# musesb.net
KiCad netlist of a schematic drawn in EAGLE
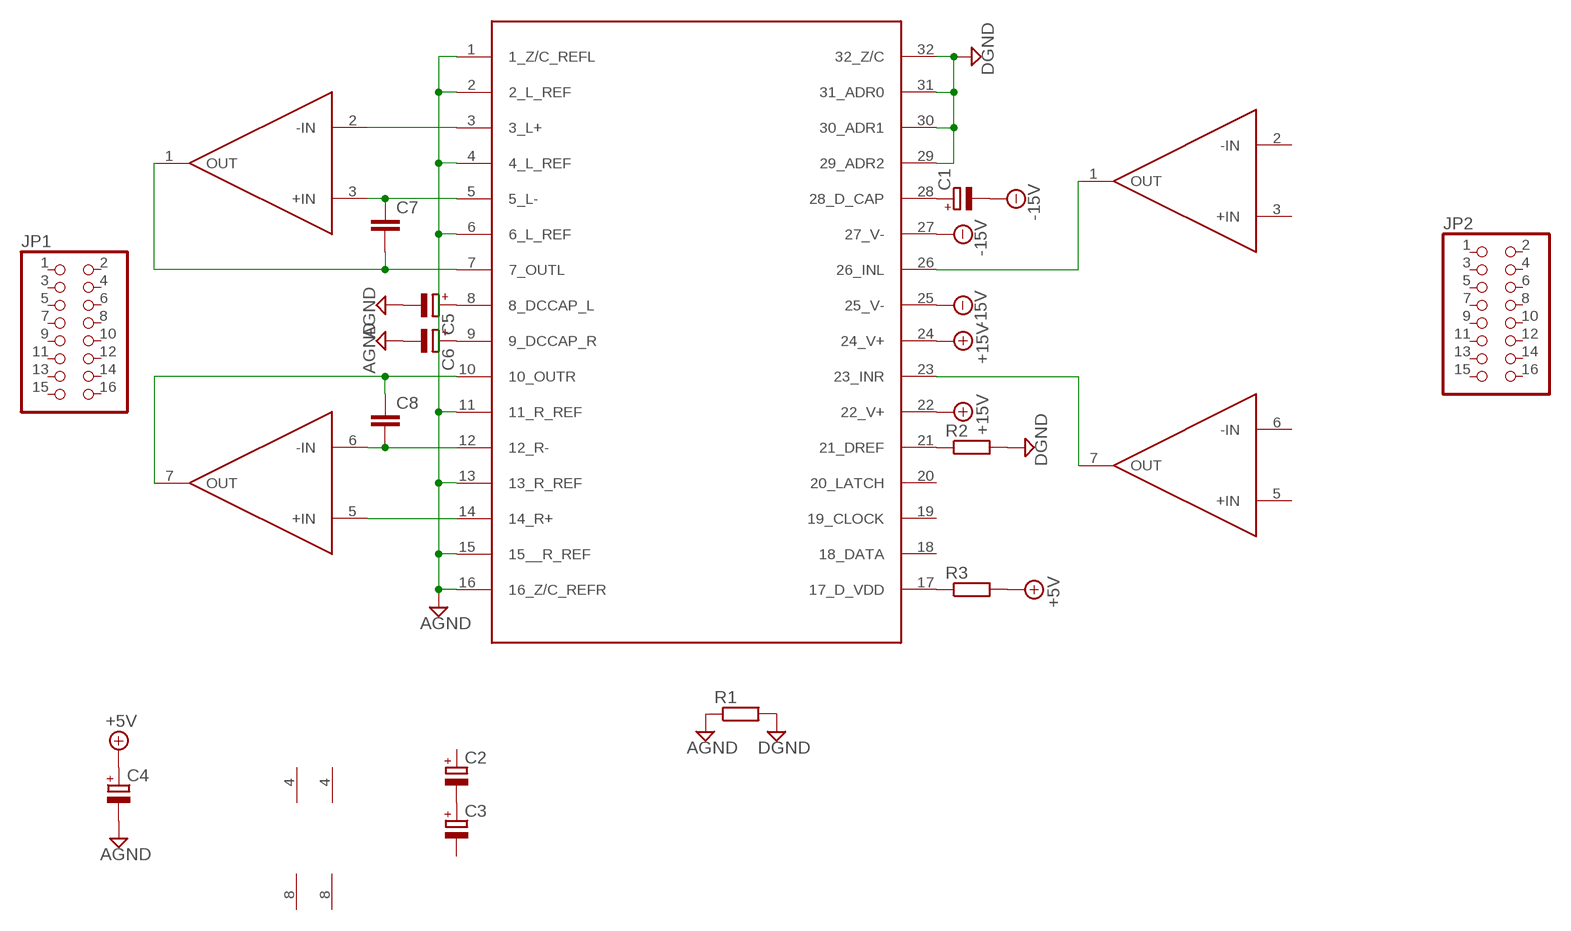
[diagram p0: schematic, sheet 1]

(export (version "E")
  (design (tool "Eeschema 10.0.6"))
  (components
    (comp (ref "C1")
      (value "CPOL-EUE2.5-6")
      (footprint "eagle-import:E2,5-6")
      (libsource (lib "eagle-import") (part "CPOL-EUE2.5-6"))
    )
    (comp (ref "C2")
      (value "CPOL-EUE3.5-8")
      (footprint "eagle-import:E3,5-8")
      (libsource (lib "eagle-import") (part "CPOL-EUE3.5-8"))
    )
    (comp (ref "C3")
      (value "CPOL-EUE3.5-8")
      (footprint "eagle-import:E3,5-8")
      (libsource (lib "eagle-import") (part "CPOL-EUE3.5-8"))
    )
    (comp (ref "C4")
      (value "CPOL-EUE3.5-8")
      (footprint "eagle-import:E3,5-8")
      (libsource (lib "eagle-import") (part "CPOL-EUE3.5-8"))
    )
    (comp (ref "C5")
      (value "CPOL-EUE3.5-8")
      (footprint "eagle-import:E3,5-8")
      (libsource (lib "eagle-import") (part "CPOL-EUE3.5-8"))
    )
    (comp (ref "C6")
      (value "CPOL-EUE3.5-8")
      (footprint "eagle-import:E3,5-8")
      (libsource (lib "eagle-import") (part "CPOL-EUE3.5-8"))
    )
    (comp (ref "C7")
      (value "C-EU025-025X050")
      (footprint "eagle-import:C025-025X050")
      (libsource (lib "eagle-import") (part "C-EU025-025X050"))
    )
    (comp (ref "C8")
      (value "C-EU025-025X050")
      (footprint "eagle-import:C025-025X050")
      (libsource (lib "eagle-import") (part "C-EU025-025X050"))
    )
    (comp (ref "JP1")
      (value "PINHD-2X8")
      (footprint "eagle-import:2X08")
      (libsource (lib "eagle-import") (part "PINHD-2X8"))
    )
    (comp (ref "JP2")
      (value "PINHD-2X8")
      (footprint "eagle-import:2X08")
      (libsource (lib "eagle-import") (part "PINHD-2X8"))
    )
    (comp (ref "R1")
      (value "R-EU_0207/7")
      (footprint "eagle-import:0207_7")
      (libsource (lib "eagle-import") (part "R-EU_0207/7"))
    )
    (comp (ref "R2")
      (value "R-EU_0207/7")
      (footprint "eagle-import:0207_7")
      (libsource (lib "eagle-import") (part "R-EU_0207/7"))
    )
    (comp (ref "R3")
      (value "R-EU_0207/7")
      (footprint "eagle-import:0207_7")
      (libsource (lib "eagle-import") (part "R-EU_0207/7"))
    )
    (comp (ref "U$1")
      (value "MUSES72320")
      (footprint "eagle-import:SSOP28DB")
      (libsource (lib "eagle-import") (part "MUSES72320"))
    )
    (comp (ref "U$2")
      (value "LME49720")
      (footprint "eagle-import:DIL08")
      (libsource (lib "eagle-import") (part "LME49720"))
    )
    (comp (ref "U$3")
      (value "LME49720")
      (footprint "eagle-import:DIL08")
      (libsource (lib "eagle-import") (part "LME49720"))
    )
  )
  (nets
    (net (code "1") (name "+5V") (class "Default")
      (node (ref "C4") (pin "+") (pinfunction "+_+") (pintype "passive"))
      (node (ref "R3") (pin "2") (pinfunction "2_2") (pintype "passive"))
    )
    (net (code "2") (name "+15V") (class "Default")
      (node (ref "U$1") (pin "22") (pinfunction "22_V+_22") (pintype "power_in"))
      (node (ref "U$1") (pin "24") (pinfunction "24_V+_24") (pintype "power_in"))
    )
    (net (code "3") (name "-15V") (class "Default")
      (node (ref "C1") (pin "-") (pinfunction "-_-") (pintype "passive"))
      (node (ref "U$1") (pin "25") (pinfunction "25_V-_25") (pintype "power_in"))
      (node (ref "U$1") (pin "27") (pinfunction "27_V-_27") (pintype "power_in"))
    )
    (net (code "4") (name "AGND") (class "Default")
      (node (ref "C4") (pin "-") (pinfunction "-_-") (pintype "passive"))
      (node (ref "C5") (pin "-") (pinfunction "-_-") (pintype "passive"))
      (node (ref "C6") (pin "-") (pinfunction "-_-") (pintype "passive"))
      (node (ref "R1") (pin "1") (pinfunction "1_1") (pintype "passive"))
      (node (ref "U$1") (pin "1") (pinfunction "1_Z/C_REFL_1") (pintype "power_in"))
      (node (ref "U$1") (pin "11") (pinfunction "11_R_REF_11") (pintype "power_in"))
      (node (ref "U$1") (pin "13") (pinfunction "13_R_REF_13") (pintype "power_in"))
      (node (ref "U$1") (pin "15") (pinfunction "15__R_REF_15") (pintype "power_in"))
      (node (ref "U$1") (pin "16") (pinfunction "16_Z/C_REFR_16") (pintype "power_in"))
      (node (ref "U$1") (pin "2") (pinfunction "2_L_REF_2") (pintype "power_in"))
      (node (ref "U$1") (pin "4") (pinfunction "4_L_REF_4") (pintype "power_in"))
      (node (ref "U$1") (pin "6") (pinfunction "6_L_REF_6") (pintype "power_in"))
    )
    (net (code "5") (name "DGND") (class "Default")
      (node (ref "R1") (pin "2") (pinfunction "2_2") (pintype "passive"))
      (node (ref "R2") (pin "2") (pinfunction "2_2") (pintype "passive"))
      (node (ref "U$1") (pin "29") (pinfunction "29_ADR2_29") (pintype "bidirectional"))
      (node (ref "U$1") (pin "30") (pinfunction "30_ADR1_30") (pintype "bidirectional"))
      (node (ref "U$1") (pin "31") (pinfunction "31_ADR0_31") (pintype "bidirectional"))
      (node (ref "U$1") (pin "32") (pinfunction "32_Z/C_32") (pintype "bidirectional"))
    )
    (net (code "6") (name "Net-(C2-Pad-)") (class "Default")
      (node (ref "C2") (pin "-") (pinfunction "-_-") (pintype "passive"))
      (node (ref "C3") (pin "+") (pinfunction "+_+") (pintype "passive"))
    )
    (net (code "7") (name "Net-(U$1-3_L+)") (class "Default")
      (node (ref "U$1") (pin "3") (pinfunction "3_L+_3") (pintype "bidirectional"))
      (node (ref "U$2") (pin "2") (pinfunction "-IN_2") (pintype "bidirectional"))
    )
    (net (code "8") (name "Net-(U$1-5_L-)") (class "Default")
      (node (ref "C7") (pin "1") (pinfunction "1_1") (pintype "passive"))
      (node (ref "U$1") (pin "5") (pinfunction "5_L-_5") (pintype "bidirectional"))
      (node (ref "U$2") (pin "3") (pinfunction "+IN_3") (pintype "bidirectional"))
    )
    (net (code "9") (name "Net-(U$1-7_OUTL)") (class "Default")
      (node (ref "C7") (pin "2") (pinfunction "2_2") (pintype "passive"))
      (node (ref "U$1") (pin "7") (pinfunction "7_OUTL_7") (pintype "bidirectional"))
      (node (ref "U$2") (pin "1") (pinfunction "OUT_1") (pintype "bidirectional"))
    )
    (net (code "10") (name "Net-(U$1-8_DCCAP_L)") (class "Default")
      (node (ref "C5") (pin "+") (pinfunction "+_+") (pintype "passive"))
      (node (ref "U$1") (pin "8") (pinfunction "8_DCCAP_L_8") (pintype "power_in"))
    )
    (net (code "11") (name "Net-(U$1-9_DCCAP_R)") (class "Default")
      (node (ref "C6") (pin "+") (pinfunction "+_+") (pintype "passive"))
      (node (ref "U$1") (pin "9") (pinfunction "9_DCCAP_R_9") (pintype "power_in"))
    )
    (net (code "12") (name "Net-(U$1-10_OUTR)") (class "Default")
      (node (ref "C8") (pin "1") (pinfunction "1_1") (pintype "passive"))
      (node (ref "U$1") (pin "10") (pinfunction "10_OUTR_10") (pintype "bidirectional"))
      (node (ref "U$2") (pin "7") (pinfunction "OUT_7") (pintype "bidirectional"))
    )
    (net (code "13") (name "Net-(U$1-12_R-)") (class "Default")
      (node (ref "C8") (pin "2") (pinfunction "2_2") (pintype "passive"))
      (node (ref "U$1") (pin "12") (pinfunction "12_R-_12") (pintype "bidirectional"))
      (node (ref "U$2") (pin "6") (pinfunction "-IN_6") (pintype "bidirectional"))
    )
    (net (code "14") (name "Net-(U$1-14_R+)") (class "Default")
      (node (ref "U$1") (pin "14") (pinfunction "14_R+_14") (pintype "bidirectional"))
      (node (ref "U$2") (pin "5") (pinfunction "+IN_5") (pintype "bidirectional"))
    )
    (net (code "15") (name "Net-(U$1-17_D_VDD)") (class "Default")
      (node (ref "R3") (pin "1") (pinfunction "1_1") (pintype "passive"))
      (node (ref "U$1") (pin "17") (pinfunction "17_D_VDD_17") (pintype "power_in"))
    )
    (net (code "16") (name "Net-(U$1-21_DREF)") (class "Default")
      (node (ref "R2") (pin "1") (pinfunction "1_1") (pintype "passive"))
      (node (ref "U$1") (pin "21") (pinfunction "21_DREF_21") (pintype "power_in"))
    )
    (net (code "17") (name "Net-(U$1-23_INR)") (class "Default")
      (node (ref "U$1") (pin "23") (pinfunction "23_INR_23") (pintype "input"))
      (node (ref "U$3") (pin "7") (pinfunction "OUT_7") (pintype "bidirectional"))
    )
    (net (code "18") (name "Net-(U$1-26_INL)") (class "Default")
      (node (ref "U$1") (pin "26") (pinfunction "26_INL_26") (pintype "input"))
      (node (ref "U$3") (pin "1") (pinfunction "OUT_1") (pintype "bidirectional"))
    )
    (net (code "19") (name "Net-(U$1-28_D_CAP)") (class "Default")
      (node (ref "C1") (pin "+") (pinfunction "+_+") (pintype "passive"))
      (node (ref "U$1") (pin "28") (pinfunction "28_D_CAP_28") (pintype "bidirectional"))
    )
    (net (code "20") (name "unconnected-(C2-Pad+)") (class "Default")
      (node (ref "C2") (pin "+") (pinfunction "+_+") (pintype "passive"))
    )
    (net (code "21") (name "unconnected-(C3-Pad-)") (class "Default")
      (node (ref "C3") (pin "-") (pinfunction "-_-") (pintype "passive"))
    )
    (net (code "22") (name "unconnected-(JP1-Pad1)") (class "Default")
      (node (ref "JP1") (pin "1") (pinfunction "1_1") (pintype "passive"))
    )
    (net (code "23") (name "unconnected-(JP1-Pad2)") (class "Default")
      (node (ref "JP1") (pin "2") (pinfunction "2_2") (pintype "passive"))
    )
    (net (code "24") (name "unconnected-(JP1-Pad3)") (class "Default")
      (node (ref "JP1") (pin "3") (pinfunction "3_3") (pintype "passive"))
    )
    (net (code "25") (name "unconnected-(JP1-Pad4)") (class "Default")
      (node (ref "JP1") (pin "4") (pinfunction "4_4") (pintype "passive"))
    )
    (net (code "26") (name "unconnected-(JP1-Pad5)") (class "Default")
      (node (ref "JP1") (pin "5") (pinfunction "5_5") (pintype "passive"))
    )
    (net (code "27") (name "unconnected-(JP1-Pad6)") (class "Default")
      (node (ref "JP1") (pin "6") (pinfunction "6_6") (pintype "passive"))
    )
    (net (code "28") (name "unconnected-(JP1-Pad7)") (class "Default")
      (node (ref "JP1") (pin "7") (pinfunction "7_7") (pintype "passive"))
    )
    (net (code "29") (name "unconnected-(JP1-Pad8)") (class "Default")
      (node (ref "JP1") (pin "8") (pinfunction "8_8") (pintype "passive"))
    )
    (net (code "30") (name "unconnected-(JP1-Pad9)") (class "Default")
      (node (ref "JP1") (pin "9") (pinfunction "9_9") (pintype "passive"))
    )
    (net (code "31") (name "unconnected-(JP1-Pad10)") (class "Default")
      (node (ref "JP1") (pin "10") (pinfunction "10_10") (pintype "passive"))
    )
    (net (code "32") (name "unconnected-(JP1-Pad11)") (class "Default")
      (node (ref "JP1") (pin "11") (pinfunction "11_11") (pintype "passive"))
    )
    (net (code "33") (name "unconnected-(JP1-Pad12)") (class "Default")
      (node (ref "JP1") (pin "12") (pinfunction "12_12") (pintype "passive"))
    )
    (net (code "34") (name "unconnected-(JP1-Pad13)") (class "Default")
      (node (ref "JP1") (pin "13") (pinfunction "13_13") (pintype "passive"))
    )
    (net (code "35") (name "unconnected-(JP1-Pad14)") (class "Default")
      (node (ref "JP1") (pin "14") (pinfunction "14_14") (pintype "passive"))
    )
    (net (code "36") (name "unconnected-(JP1-Pad15)") (class "Default")
      (node (ref "JP1") (pin "15") (pinfunction "15_15") (pintype "passive"))
    )
    (net (code "37") (name "unconnected-(JP1-Pad16)") (class "Default")
      (node (ref "JP1") (pin "16") (pinfunction "16_16") (pintype "passive"))
    )
    (net (code "38") (name "unconnected-(JP2-Pad1)") (class "Default")
      (node (ref "JP2") (pin "1") (pinfunction "1_1") (pintype "passive"))
    )
    (net (code "39") (name "unconnected-(JP2-Pad2)") (class "Default")
      (node (ref "JP2") (pin "2") (pinfunction "2_2") (pintype "passive"))
    )
    (net (code "40") (name "unconnected-(JP2-Pad3)") (class "Default")
      (node (ref "JP2") (pin "3") (pinfunction "3_3") (pintype "passive"))
    )
    (net (code "41") (name "unconnected-(JP2-Pad4)") (class "Default")
      (node (ref "JP2") (pin "4") (pinfunction "4_4") (pintype "passive"))
    )
    (net (code "42") (name "unconnected-(JP2-Pad5)") (class "Default")
      (node (ref "JP2") (pin "5") (pinfunction "5_5") (pintype "passive"))
    )
    (net (code "43") (name "unconnected-(JP2-Pad6)") (class "Default")
      (node (ref "JP2") (pin "6") (pinfunction "6_6") (pintype "passive"))
    )
    (net (code "44") (name "unconnected-(JP2-Pad7)") (class "Default")
      (node (ref "JP2") (pin "7") (pinfunction "7_7") (pintype "passive"))
    )
    (net (code "45") (name "unconnected-(JP2-Pad8)") (class "Default")
      (node (ref "JP2") (pin "8") (pinfunction "8_8") (pintype "passive"))
    )
    (net (code "46") (name "unconnected-(JP2-Pad9)") (class "Default")
      (node (ref "JP2") (pin "9") (pinfunction "9_9") (pintype "passive"))
    )
    (net (code "47") (name "unconnected-(JP2-Pad10)") (class "Default")
      (node (ref "JP2") (pin "10") (pinfunction "10_10") (pintype "passive"))
    )
    (net (code "48") (name "unconnected-(JP2-Pad11)") (class "Default")
      (node (ref "JP2") (pin "11") (pinfunction "11_11") (pintype "passive"))
    )
    (net (code "49") (name "unconnected-(JP2-Pad12)") (class "Default")
      (node (ref "JP2") (pin "12") (pinfunction "12_12") (pintype "passive"))
    )
    (net (code "50") (name "unconnected-(JP2-Pad13)") (class "Default")
      (node (ref "JP2") (pin "13") (pinfunction "13_13") (pintype "passive"))
    )
    (net (code "51") (name "unconnected-(JP2-Pad14)") (class "Default")
      (node (ref "JP2") (pin "14") (pinfunction "14_14") (pintype "passive"))
    )
    (net (code "52") (name "unconnected-(JP2-Pad15)") (class "Default")
      (node (ref "JP2") (pin "15") (pinfunction "15_15") (pintype "passive"))
    )
    (net (code "53") (name "unconnected-(JP2-Pad16)") (class "Default")
      (node (ref "JP2") (pin "16") (pinfunction "16_16") (pintype "passive"))
    )
    (net (code "54") (name "unconnected-(U$1-18_DATA-Pad18)") (class "Default")
      (node (ref "U$1") (pin "18") (pinfunction "18_DATA_18") (pintype "bidirectional"))
    )
    (net (code "55") (name "unconnected-(U$1-19_CLOCK-Pad19)") (class "Default")
      (node (ref "U$1") (pin "19") (pinfunction "19_CLOCK_19") (pintype "bidirectional"))
    )
    (net (code "56") (name "unconnected-(U$1-20_LATCH-Pad20)") (class "Default")
      (node (ref "U$1") (pin "20") (pinfunction "20_LATCH_20") (pintype "bidirectional"))
    )
    (net (code "57") (name "unconnected-(U$2C-V+-Pad8)") (class "Default")
      (node (ref "U$2") (pin "8") (pinfunction "V+_8") (pintype "bidirectional"))
    )
    (net (code "58") (name "unconnected-(U$2C-V--Pad4)") (class "Default")
      (node (ref "U$2") (pin "4") (pinfunction "V-_4") (pintype "bidirectional"))
    )
    (net (code "59") (name "unconnected-(U$3A-+IN-Pad3)") (class "Default")
      (node (ref "U$3") (pin "3") (pinfunction "+IN_3") (pintype "bidirectional"))
    )
    (net (code "60") (name "unconnected-(U$3A--IN-Pad2)") (class "Default")
      (node (ref "U$3") (pin "2") (pinfunction "-IN_2") (pintype "bidirectional"))
    )
    (net (code "61") (name "unconnected-(U$3B-+IN-Pad5)") (class "Default")
      (node (ref "U$3") (pin "5") (pinfunction "+IN_5") (pintype "bidirectional"))
    )
    (net (code "62") (name "unconnected-(U$3B--IN-Pad6)") (class "Default")
      (node (ref "U$3") (pin "6") (pinfunction "-IN_6") (pintype "bidirectional"))
    )
    (net (code "63") (name "unconnected-(U$3C-V+-Pad8)") (class "Default")
      (node (ref "U$3") (pin "8") (pinfunction "V+_8") (pintype "bidirectional"))
    )
    (net (code "64") (name "unconnected-(U$3C-V--Pad4)") (class "Default")
      (node (ref "U$3") (pin "4") (pinfunction "V-_4") (pintype "bidirectional"))
    )
  )
)
